# Skaarhoj_BI8-1x12CAP3slim.net
KiCad netlist of a schematic drawn in EAGLE
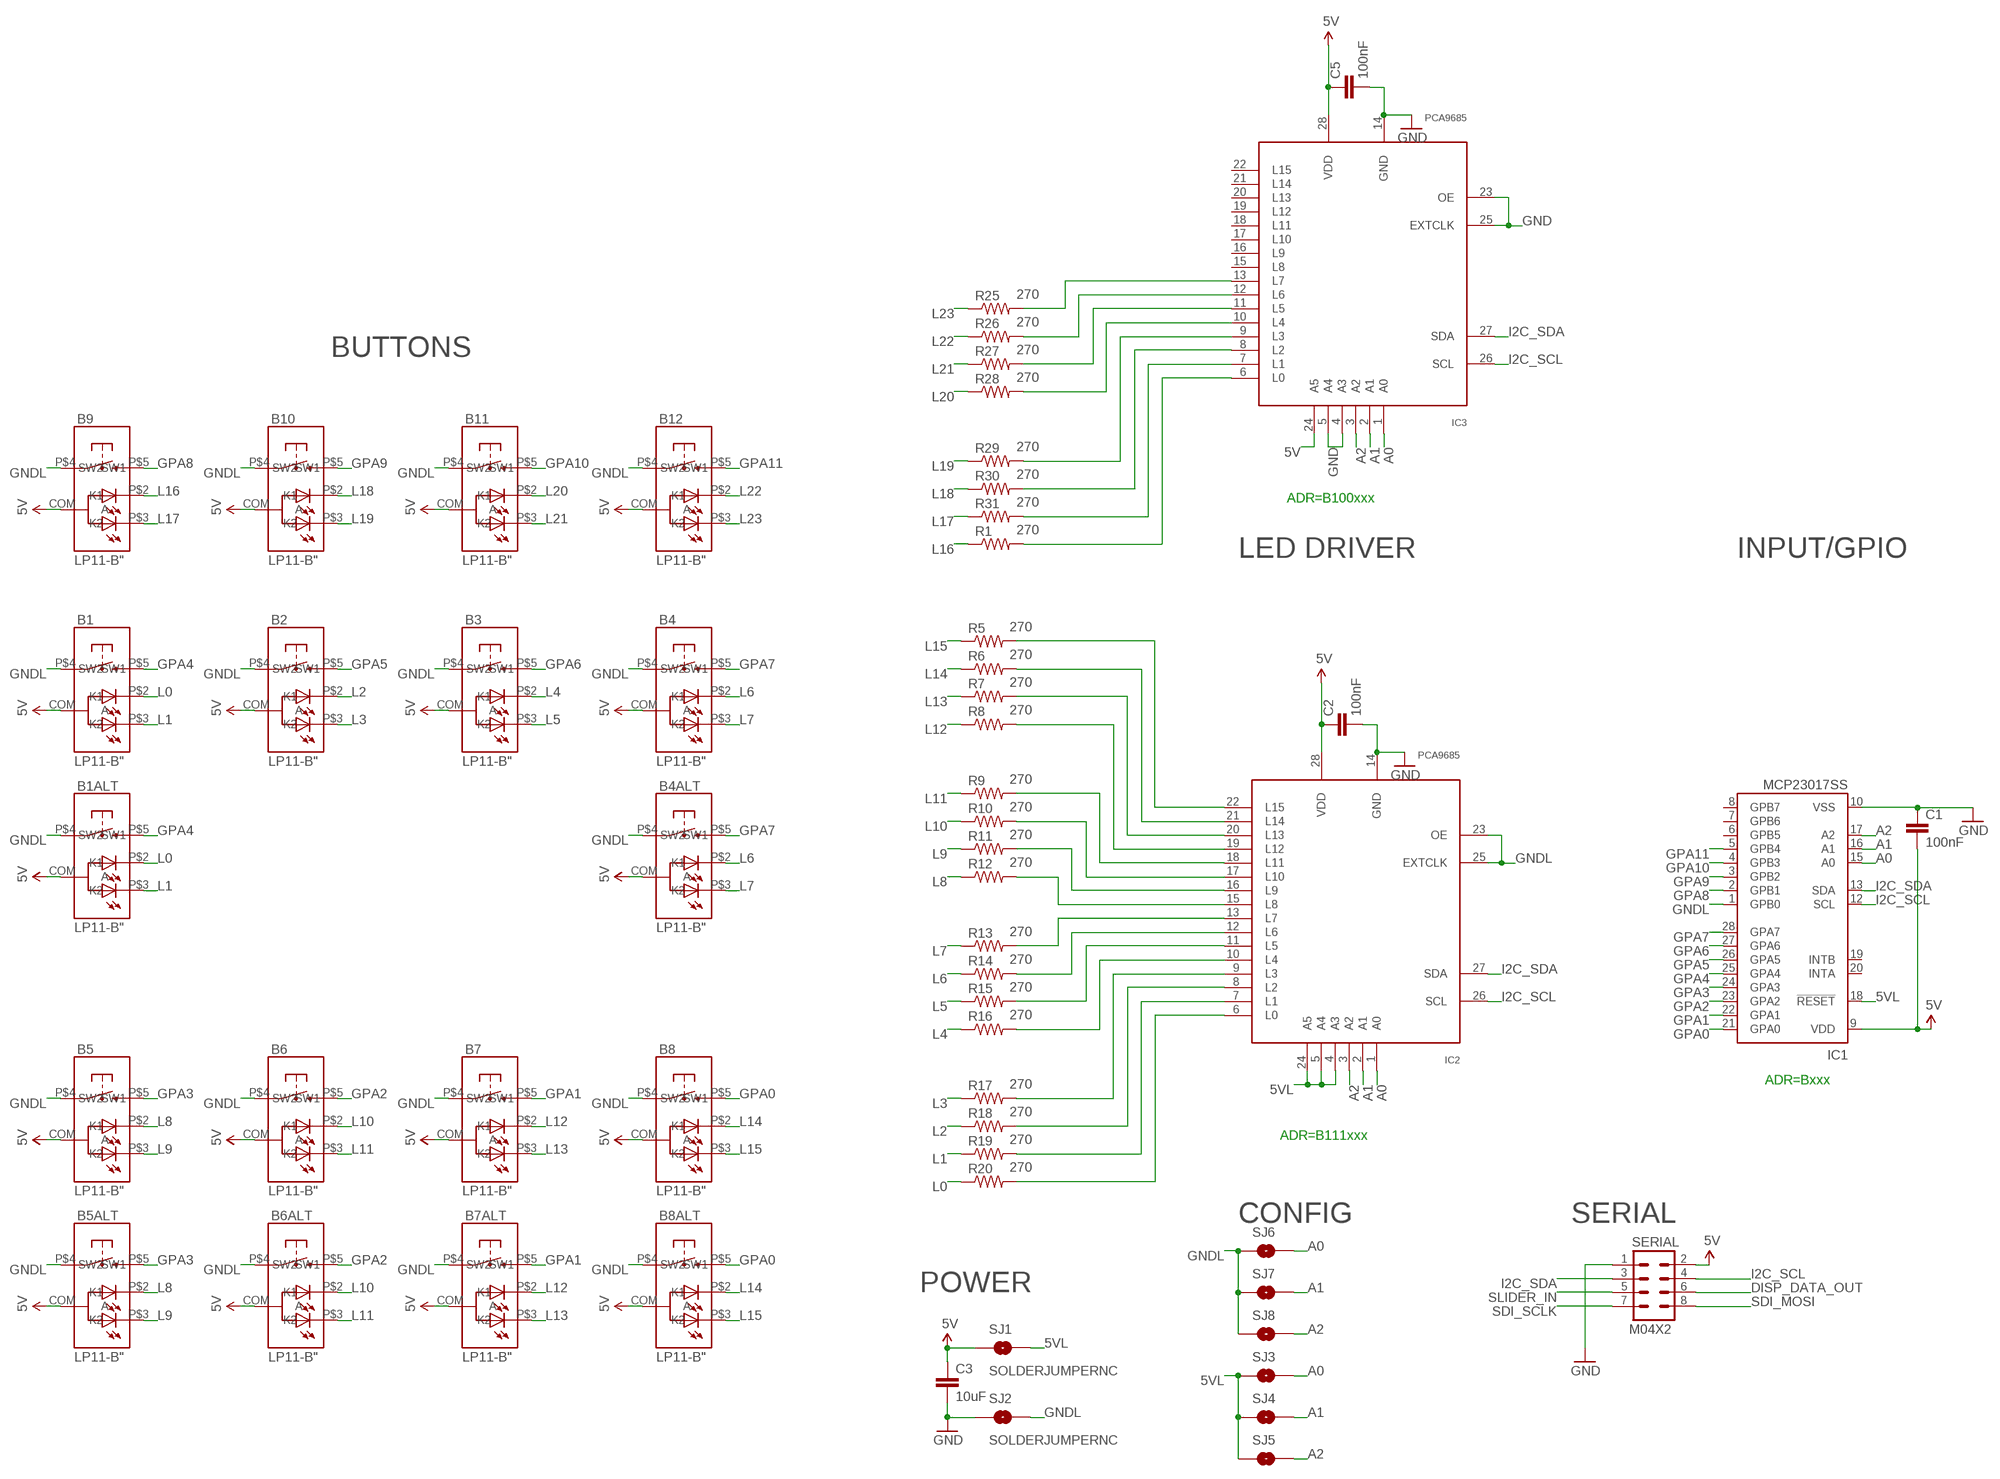
[diagram p0: schematic, sheet 1]

(export (version "E")
  (design (tool "Eeschema 10.0.6"))
  (components
    (comp (ref "B1")
      (value "LP11-B\"")
      (footprint "eagle-import:LP11")
      (libsource (lib "eagle-import") (part "LP11-B{dblquote}"))
    )
    (comp (ref "B1ALT")
      (value "LP11-B\"")
      (footprint "eagle-import:LP11")
      (libsource (lib "eagle-import") (part "LP11-B{dblquote}"))
    )
    (comp (ref "B2")
      (value "LP11-B\"")
      (footprint "eagle-import:LP11")
      (libsource (lib "eagle-import") (part "LP11-B{dblquote}"))
    )
    (comp (ref "B3")
      (value "LP11-B\"")
      (footprint "eagle-import:LP11")
      (libsource (lib "eagle-import") (part "LP11-B{dblquote}"))
    )
    (comp (ref "B4")
      (value "LP11-B\"")
      (footprint "eagle-import:LP11")
      (libsource (lib "eagle-import") (part "LP11-B{dblquote}"))
    )
    (comp (ref "B4ALT")
      (value "LP11-B\"")
      (footprint "eagle-import:LP11")
      (libsource (lib "eagle-import") (part "LP11-B{dblquote}"))
    )
    (comp (ref "B5")
      (value "LP11-B\"")
      (footprint "eagle-import:LP11")
      (libsource (lib "eagle-import") (part "LP11-B{dblquote}"))
    )
    (comp (ref "B5ALT")
      (value "LP11-B\"")
      (footprint "eagle-import:LP11")
      (libsource (lib "eagle-import") (part "LP11-B{dblquote}"))
    )
    (comp (ref "B6")
      (value "LP11-B\"")
      (footprint "eagle-import:LP11")
      (libsource (lib "eagle-import") (part "LP11-B{dblquote}"))
    )
    (comp (ref "B6ALT")
      (value "LP11-B\"")
      (footprint "eagle-import:LP11")
      (libsource (lib "eagle-import") (part "LP11-B{dblquote}"))
    )
    (comp (ref "B7")
      (value "LP11-B\"")
      (footprint "eagle-import:LP11")
      (libsource (lib "eagle-import") (part "LP11-B{dblquote}"))
    )
    (comp (ref "B7ALT")
      (value "LP11-B\"")
      (footprint "eagle-import:LP11")
      (libsource (lib "eagle-import") (part "LP11-B{dblquote}"))
    )
    (comp (ref "B8")
      (value "LP11-B\"")
      (footprint "eagle-import:LP11")
      (libsource (lib "eagle-import") (part "LP11-B{dblquote}"))
    )
    (comp (ref "B8ALT")
      (value "LP11-B\"")
      (footprint "eagle-import:LP11")
      (libsource (lib "eagle-import") (part "LP11-B{dblquote}"))
    )
    (comp (ref "B9")
      (value "LP11-B\"")
      (footprint "eagle-import:LP11")
      (libsource (lib "eagle-import") (part "LP11-B{dblquote}"))
    )
    (comp (ref "B10")
      (value "LP11-B\"")
      (footprint "eagle-import:LP11")
      (libsource (lib "eagle-import") (part "LP11-B{dblquote}"))
    )
    (comp (ref "B11")
      (value "LP11-B\"")
      (footprint "eagle-import:LP11")
      (libsource (lib "eagle-import") (part "LP11-B{dblquote}"))
    )
    (comp (ref "B12")
      (value "LP11-B\"")
      (footprint "eagle-import:LP11")
      (libsource (lib "eagle-import") (part "LP11-B{dblquote}"))
    )
    (comp (ref "C1")
      (value "100nF")
      (footprint "eagle-import:0603-CAP")
      (libsource (lib "eagle-import") (part "CAP0603-CAP"))
    )
    (comp (ref "C2")
      (value "100nF")
      (footprint "eagle-import:0603-CAP")
      (libsource (lib "eagle-import") (part "CAP0603-CAP"))
    )
    (comp (ref "C3")
      (value "10uF")
      (footprint "eagle-import:0805")
      (libsource (lib "eagle-import") (part "CAP0805"))
    )
    (comp (ref "C5")
      (value "100nF")
      (footprint "eagle-import:0603-CAP")
      (libsource (lib "eagle-import") (part "CAP0603-CAP"))
    )
    (comp (ref "IC1")
      (value "MCP23017SS")
      (footprint "eagle-import:SSOP28")
      (fields
        (field (name "MF") "MICROCHIP")
        (field (name "MPN") "MCP23017-E/SS")
        (field (name "MPN_1") "MCP23017-E/SS")
        (field (name "OC_FARNELL") "1467674")
        (field (name "OC_NEWARK") "31K2960")
      )
      (libsource (lib "eagle-import") (part "MCP23017SS"))
    )
    (comp (ref "IC2")
      (value "PCA9685")
      (footprint "eagle-import:TSSOP28")
      (libsource (lib "eagle-import") (part "PCA9685"))
    )
    (comp (ref "IC3")
      (value "PCA9685")
      (footprint "eagle-import:TSSOP28")
      (libsource (lib "eagle-import") (part "PCA9685"))
    )
    (comp (ref "R1")
      (value "270")
      (footprint "eagle-import:0603-RES")
      (libsource (lib "eagle-import") (part "RESISTOR0603-RES"))
    )
    (comp (ref "R5")
      (value "270")
      (footprint "eagle-import:0603-RES")
      (libsource (lib "eagle-import") (part "RESISTOR0603-RES"))
    )
    (comp (ref "R6")
      (value "270")
      (footprint "eagle-import:0603-RES")
      (libsource (lib "eagle-import") (part "RESISTOR0603-RES"))
    )
    (comp (ref "R7")
      (value "270")
      (footprint "eagle-import:0603-RES")
      (libsource (lib "eagle-import") (part "RESISTOR0603-RES"))
    )
    (comp (ref "R8")
      (value "270")
      (footprint "eagle-import:0603-RES")
      (libsource (lib "eagle-import") (part "RESISTOR0603-RES"))
    )
    (comp (ref "R9")
      (value "270")
      (footprint "eagle-import:0603-RES")
      (libsource (lib "eagle-import") (part "RESISTOR0603-RES"))
    )
    (comp (ref "R10")
      (value "270")
      (footprint "eagle-import:0603-RES")
      (libsource (lib "eagle-import") (part "RESISTOR0603-RES"))
    )
    (comp (ref "R11")
      (value "270")
      (footprint "eagle-import:0603-RES")
      (libsource (lib "eagle-import") (part "RESISTOR0603-RES"))
    )
    (comp (ref "R12")
      (value "270")
      (footprint "eagle-import:0603-RES")
      (libsource (lib "eagle-import") (part "RESISTOR0603-RES"))
    )
    (comp (ref "R13")
      (value "270")
      (footprint "eagle-import:0603-RES")
      (libsource (lib "eagle-import") (part "RESISTOR0603-RES"))
    )
    (comp (ref "R14")
      (value "270")
      (footprint "eagle-import:0603-RES")
      (libsource (lib "eagle-import") (part "RESISTOR0603-RES"))
    )
    (comp (ref "R15")
      (value "270")
      (footprint "eagle-import:0603-RES")
      (libsource (lib "eagle-import") (part "RESISTOR0603-RES"))
    )
    (comp (ref "R16")
      (value "270")
      (footprint "eagle-import:0603-RES")
      (libsource (lib "eagle-import") (part "RESISTOR0603-RES"))
    )
    (comp (ref "R17")
      (value "270")
      (footprint "eagle-import:0603-RES")
      (libsource (lib "eagle-import") (part "RESISTOR0603-RES"))
    )
    (comp (ref "R18")
      (value "270")
      (footprint "eagle-import:0603-RES")
      (libsource (lib "eagle-import") (part "RESISTOR0603-RES"))
    )
    (comp (ref "R19")
      (value "270")
      (footprint "eagle-import:0603-RES")
      (libsource (lib "eagle-import") (part "RESISTOR0603-RES"))
    )
    (comp (ref "R20")
      (value "270")
      (footprint "eagle-import:0603-RES")
      (libsource (lib "eagle-import") (part "RESISTOR0603-RES"))
    )
    (comp (ref "R25")
      (value "270")
      (footprint "eagle-import:0603-RES")
      (libsource (lib "eagle-import") (part "RESISTOR0603-RES"))
    )
    (comp (ref "R26")
      (value "270")
      (footprint "eagle-import:0603-RES")
      (libsource (lib "eagle-import") (part "RESISTOR0603-RES"))
    )
    (comp (ref "R27")
      (value "270")
      (footprint "eagle-import:0603-RES")
      (libsource (lib "eagle-import") (part "RESISTOR0603-RES"))
    )
    (comp (ref "R28")
      (value "270")
      (footprint "eagle-import:0603-RES")
      (libsource (lib "eagle-import") (part "RESISTOR0603-RES"))
    )
    (comp (ref "R29")
      (value "270")
      (footprint "eagle-import:0603-RES")
      (libsource (lib "eagle-import") (part "RESISTOR0603-RES"))
    )
    (comp (ref "R30")
      (value "270")
      (footprint "eagle-import:0603-RES")
      (libsource (lib "eagle-import") (part "RESISTOR0603-RES"))
    )
    (comp (ref "R31")
      (value "270")
      (footprint "eagle-import:0603-RES")
      (libsource (lib "eagle-import") (part "RESISTOR0603-RES"))
    )
    (comp (ref "SERIAL")
      (value "M04X2")
      (footprint "eagle-import:2X4")
      (libsource (lib "eagle-import") (part "M04X2"))
    )
    (comp (ref "SJ1")
      (value "SOLDERJUMPERNC")
      (footprint "eagle-import:SJ_2S")
      (libsource (lib "eagle-import") (part "SOLDERJUMPERNC"))
    )
    (comp (ref "SJ2")
      (value "SOLDERJUMPERNC")
      (footprint "eagle-import:SJ_2S")
      (libsource (lib "eagle-import") (part "SOLDERJUMPERNC"))
    )
    (comp (ref "SJ3")
      (value "SOLDERJUMPERNC")
      (footprint "eagle-import:SJ_2S")
      (libsource (lib "eagle-import") (part "SOLDERJUMPERNC"))
    )
    (comp (ref "SJ4")
      (value "SOLDERJUMPERNC")
      (footprint "eagle-import:SJ_2S")
      (libsource (lib "eagle-import") (part "SOLDERJUMPERNC"))
    )
    (comp (ref "SJ5")
      (value "SOLDERJUMPERNC")
      (footprint "eagle-import:SJ_2S")
      (libsource (lib "eagle-import") (part "SOLDERJUMPERNC"))
    )
    (comp (ref "SJ6")
      (value "SOLDERJUMPERNC")
      (footprint "eagle-import:SJ_2S")
      (libsource (lib "eagle-import") (part "SOLDERJUMPERNC"))
    )
    (comp (ref "SJ7")
      (value "SOLDERJUMPERNC")
      (footprint "eagle-import:SJ_2S")
      (libsource (lib "eagle-import") (part "SOLDERJUMPERNC"))
    )
    (comp (ref "SJ8")
      (value "SOLDERJUMPERNC")
      (footprint "eagle-import:SJ_2S")
      (libsource (lib "eagle-import") (part "SOLDERJUMPERNC"))
    )
  )
  (nets
    (net (code "1") (name "/5VL") (class "Default")
      (node (ref "IC1") (pin "18") (pinfunction "~{RESET}_18") (pintype "input"))
      (node (ref "IC2") (pin "24") (pinfunction "A5_24") (pintype "input"))
      (node (ref "IC2") (pin "4") (pinfunction "A3_4") (pintype "input"))
      (node (ref "IC2") (pin "5") (pinfunction "A4_5") (pintype "input"))
      (node (ref "SJ1") (pin "2") (pinfunction "2_2") (pintype "passive"))
      (node (ref "SJ3") (pin "1") (pinfunction "1_1") (pintype "passive"))
      (node (ref "SJ4") (pin "1") (pinfunction "1_1") (pintype "passive"))
      (node (ref "SJ5") (pin "1") (pinfunction "1_1") (pintype "passive"))
    )
    (net (code "2") (name "/A0") (class "Default")
      (node (ref "IC1") (pin "15") (pinfunction "A0_15") (pintype "input"))
      (node (ref "IC2") (pin "1") (pinfunction "A0_1") (pintype "input"))
      (node (ref "IC3") (pin "1") (pinfunction "A0_1") (pintype "input"))
      (node (ref "SJ3") (pin "2") (pinfunction "2_2") (pintype "passive"))
      (node (ref "SJ6") (pin "2") (pinfunction "2_2") (pintype "passive"))
    )
    (net (code "3") (name "/A1") (class "Default")
      (node (ref "IC1") (pin "16") (pinfunction "A1_16") (pintype "input"))
      (node (ref "IC2") (pin "2") (pinfunction "A1_2") (pintype "input"))
      (node (ref "IC3") (pin "2") (pinfunction "A1_2") (pintype "input"))
      (node (ref "SJ4") (pin "2") (pinfunction "2_2") (pintype "passive"))
      (node (ref "SJ7") (pin "2") (pinfunction "2_2") (pintype "passive"))
    )
    (net (code "4") (name "/A2") (class "Default")
      (node (ref "IC1") (pin "17") (pinfunction "A2_17") (pintype "input"))
      (node (ref "IC2") (pin "3") (pinfunction "A2_3") (pintype "input"))
      (node (ref "IC3") (pin "3") (pinfunction "A2_3") (pintype "input"))
      (node (ref "SJ5") (pin "2") (pinfunction "2_2") (pintype "passive"))
      (node (ref "SJ8") (pin "2") (pinfunction "2_2") (pintype "passive"))
    )
    (net (code "5") (name "/DISP_DATA_OUT") (class "Default")
      (node (ref "SERIAL") (pin "6") (pinfunction "6_6") (pintype "passive"))
    )
    (net (code "6") (name "/GNDL") (class "Default")
      (node (ref "B1") (pin "P$4") (pinfunction "SW1_P$4") (pintype "bidirectional"))
      (node (ref "B10") (pin "P$4") (pinfunction "SW1_P$4") (pintype "bidirectional"))
      (node (ref "B11") (pin "P$4") (pinfunction "SW1_P$4") (pintype "bidirectional"))
      (node (ref "B12") (pin "P$4") (pinfunction "SW1_P$4") (pintype "bidirectional"))
      (node (ref "B1ALT") (pin "P$4") (pinfunction "SW1_P$4") (pintype "bidirectional"))
      (node (ref "B2") (pin "P$4") (pinfunction "SW1_P$4") (pintype "bidirectional"))
      (node (ref "B3") (pin "P$4") (pinfunction "SW1_P$4") (pintype "bidirectional"))
      (node (ref "B4") (pin "P$4") (pinfunction "SW1_P$4") (pintype "bidirectional"))
      (node (ref "B4ALT") (pin "P$4") (pinfunction "SW1_P$4") (pintype "bidirectional"))
      (node (ref "B5") (pin "P$4") (pinfunction "SW1_P$4") (pintype "bidirectional"))
      (node (ref "B5ALT") (pin "P$4") (pinfunction "SW1_P$4") (pintype "bidirectional"))
      (node (ref "B6") (pin "P$4") (pinfunction "SW1_P$4") (pintype "bidirectional"))
      (node (ref "B6ALT") (pin "P$4") (pinfunction "SW1_P$4") (pintype "bidirectional"))
      (node (ref "B7") (pin "P$4") (pinfunction "SW1_P$4") (pintype "bidirectional"))
      (node (ref "B7ALT") (pin "P$4") (pinfunction "SW1_P$4") (pintype "bidirectional"))
      (node (ref "B8") (pin "P$4") (pinfunction "SW1_P$4") (pintype "bidirectional"))
      (node (ref "B8ALT") (pin "P$4") (pinfunction "SW1_P$4") (pintype "bidirectional"))
      (node (ref "B9") (pin "P$4") (pinfunction "SW1_P$4") (pintype "bidirectional"))
      (node (ref "IC1") (pin "1") (pinfunction "GPB0_1") (pintype "bidirectional"))
      (node (ref "IC2") (pin "23") (pinfunction "OE_23") (pintype "input"))
      (node (ref "IC2") (pin "25") (pinfunction "EXTCLK_25") (pintype "input"))
      (node (ref "SJ2") (pin "2") (pinfunction "2_2") (pintype "passive"))
      (node (ref "SJ6") (pin "1") (pinfunction "1_1") (pintype "passive"))
      (node (ref "SJ7") (pin "1") (pinfunction "1_1") (pintype "passive"))
      (node (ref "SJ8") (pin "1") (pinfunction "1_1") (pintype "passive"))
    )
    (net (code "7") (name "/GPA0") (class "Default")
      (node (ref "B8") (pin "P$5") (pinfunction "SW2_P$5") (pintype "bidirectional"))
      (node (ref "B8ALT") (pin "P$5") (pinfunction "SW2_P$5") (pintype "bidirectional"))
      (node (ref "IC1") (pin "21") (pinfunction "GPA0_21") (pintype "bidirectional"))
    )
    (net (code "8") (name "/GPA1") (class "Default")
      (node (ref "B7") (pin "P$5") (pinfunction "SW2_P$5") (pintype "bidirectional"))
      (node (ref "B7ALT") (pin "P$5") (pinfunction "SW2_P$5") (pintype "bidirectional"))
      (node (ref "IC1") (pin "22") (pinfunction "GPA1_22") (pintype "bidirectional"))
    )
    (net (code "9") (name "/GPA2") (class "Default")
      (node (ref "B6") (pin "P$5") (pinfunction "SW2_P$5") (pintype "bidirectional"))
      (node (ref "B6ALT") (pin "P$5") (pinfunction "SW2_P$5") (pintype "bidirectional"))
      (node (ref "IC1") (pin "23") (pinfunction "GPA2_23") (pintype "bidirectional"))
    )
    (net (code "10") (name "/GPA3") (class "Default")
      (node (ref "B5") (pin "P$5") (pinfunction "SW2_P$5") (pintype "bidirectional"))
      (node (ref "B5ALT") (pin "P$5") (pinfunction "SW2_P$5") (pintype "bidirectional"))
      (node (ref "IC1") (pin "24") (pinfunction "GPA3_24") (pintype "bidirectional"))
    )
    (net (code "11") (name "/GPA4") (class "Default")
      (node (ref "B1") (pin "P$5") (pinfunction "SW2_P$5") (pintype "bidirectional"))
      (node (ref "B1ALT") (pin "P$5") (pinfunction "SW2_P$5") (pintype "bidirectional"))
      (node (ref "IC1") (pin "25") (pinfunction "GPA4_25") (pintype "bidirectional"))
    )
    (net (code "12") (name "/GPA5") (class "Default")
      (node (ref "B2") (pin "P$5") (pinfunction "SW2_P$5") (pintype "bidirectional"))
      (node (ref "IC1") (pin "26") (pinfunction "GPA5_26") (pintype "bidirectional"))
    )
    (net (code "13") (name "/GPA6") (class "Default")
      (node (ref "B3") (pin "P$5") (pinfunction "SW2_P$5") (pintype "bidirectional"))
      (node (ref "IC1") (pin "27") (pinfunction "GPA6_27") (pintype "bidirectional"))
    )
    (net (code "14") (name "/GPA7") (class "Default")
      (node (ref "B4") (pin "P$5") (pinfunction "SW2_P$5") (pintype "bidirectional"))
      (node (ref "B4ALT") (pin "P$5") (pinfunction "SW2_P$5") (pintype "bidirectional"))
      (node (ref "IC1") (pin "28") (pinfunction "GPA7_28") (pintype "bidirectional"))
    )
    (net (code "15") (name "/GPA8") (class "Default")
      (node (ref "B9") (pin "P$5") (pinfunction "SW2_P$5") (pintype "bidirectional"))
      (node (ref "IC1") (pin "2") (pinfunction "GPB1_2") (pintype "bidirectional"))
    )
    (net (code "16") (name "/GPA9") (class "Default")
      (node (ref "B10") (pin "P$5") (pinfunction "SW2_P$5") (pintype "bidirectional"))
      (node (ref "IC1") (pin "3") (pinfunction "GPB2_3") (pintype "bidirectional"))
    )
    (net (code "17") (name "/GPA10") (class "Default")
      (node (ref "B11") (pin "P$5") (pinfunction "SW2_P$5") (pintype "bidirectional"))
      (node (ref "IC1") (pin "4") (pinfunction "GPB3_4") (pintype "bidirectional"))
    )
    (net (code "18") (name "/GPA11") (class "Default")
      (node (ref "B12") (pin "P$5") (pinfunction "SW2_P$5") (pintype "bidirectional"))
      (node (ref "IC1") (pin "5") (pinfunction "GPB4_5") (pintype "bidirectional"))
    )
    (net (code "19") (name "/I2C_SCL") (class "Default")
      (node (ref "IC1") (pin "12") (pinfunction "SCL_12") (pintype "input"))
      (node (ref "IC2") (pin "26") (pinfunction "SCL_26") (pintype "input"))
      (node (ref "IC3") (pin "26") (pinfunction "SCL_26") (pintype "input"))
      (node (ref "SERIAL") (pin "4") (pinfunction "4_4") (pintype "passive"))
    )
    (net (code "20") (name "/I2C_SDA") (class "Default")
      (node (ref "IC1") (pin "13") (pinfunction "SDA_13") (pintype "bidirectional"))
      (node (ref "IC2") (pin "27") (pinfunction "SDA_27") (pintype "input"))
      (node (ref "IC3") (pin "27") (pinfunction "SDA_27") (pintype "input"))
      (node (ref "SERIAL") (pin "3") (pinfunction "3_3") (pintype "passive"))
    )
    (net (code "21") (name "/L0") (class "Default")
      (node (ref "B1") (pin "P$2") (pinfunction "K1_P$2") (pintype "bidirectional"))
      (node (ref "B1ALT") (pin "P$2") (pinfunction "K1_P$2") (pintype "bidirectional"))
      (node (ref "R20") (pin "1") (pinfunction "1_1") (pintype "passive"))
    )
    (net (code "22") (name "/L1") (class "Default")
      (node (ref "B1") (pin "P$3") (pinfunction "K2_P$3") (pintype "bidirectional"))
      (node (ref "B1ALT") (pin "P$3") (pinfunction "K2_P$3") (pintype "bidirectional"))
      (node (ref "R19") (pin "1") (pinfunction "1_1") (pintype "passive"))
    )
    (net (code "23") (name "/L2") (class "Default")
      (node (ref "B2") (pin "P$2") (pinfunction "K1_P$2") (pintype "bidirectional"))
      (node (ref "R18") (pin "1") (pinfunction "1_1") (pintype "passive"))
    )
    (net (code "24") (name "/L3") (class "Default")
      (node (ref "B2") (pin "P$3") (pinfunction "K2_P$3") (pintype "bidirectional"))
      (node (ref "R17") (pin "1") (pinfunction "1_1") (pintype "passive"))
    )
    (net (code "25") (name "/L4") (class "Default")
      (node (ref "B3") (pin "P$2") (pinfunction "K1_P$2") (pintype "bidirectional"))
      (node (ref "R16") (pin "1") (pinfunction "1_1") (pintype "passive"))
    )
    (net (code "26") (name "/L5") (class "Default")
      (node (ref "B3") (pin "P$3") (pinfunction "K2_P$3") (pintype "bidirectional"))
      (node (ref "R15") (pin "1") (pinfunction "1_1") (pintype "passive"))
    )
    (net (code "27") (name "/L6") (class "Default")
      (node (ref "B4") (pin "P$2") (pinfunction "K1_P$2") (pintype "bidirectional"))
      (node (ref "B4ALT") (pin "P$2") (pinfunction "K1_P$2") (pintype "bidirectional"))
      (node (ref "R14") (pin "1") (pinfunction "1_1") (pintype "passive"))
    )
    (net (code "28") (name "/L7") (class "Default")
      (node (ref "B4") (pin "P$3") (pinfunction "K2_P$3") (pintype "bidirectional"))
      (node (ref "B4ALT") (pin "P$3") (pinfunction "K2_P$3") (pintype "bidirectional"))
      (node (ref "R13") (pin "1") (pinfunction "1_1") (pintype "passive"))
    )
    (net (code "29") (name "/L8") (class "Default")
      (node (ref "B5") (pin "P$2") (pinfunction "K1_P$2") (pintype "bidirectional"))
      (node (ref "B5ALT") (pin "P$2") (pinfunction "K1_P$2") (pintype "bidirectional"))
      (node (ref "R12") (pin "1") (pinfunction "1_1") (pintype "passive"))
    )
    (net (code "30") (name "/L9") (class "Default")
      (node (ref "B5") (pin "P$3") (pinfunction "K2_P$3") (pintype "bidirectional"))
      (node (ref "B5ALT") (pin "P$3") (pinfunction "K2_P$3") (pintype "bidirectional"))
      (node (ref "R11") (pin "1") (pinfunction "1_1") (pintype "passive"))
    )
    (net (code "31") (name "/L10") (class "Default")
      (node (ref "B6") (pin "P$2") (pinfunction "K1_P$2") (pintype "bidirectional"))
      (node (ref "B6ALT") (pin "P$2") (pinfunction "K1_P$2") (pintype "bidirectional"))
      (node (ref "R10") (pin "1") (pinfunction "1_1") (pintype "passive"))
    )
    (net (code "32") (name "/L11") (class "Default")
      (node (ref "B6") (pin "P$3") (pinfunction "K2_P$3") (pintype "bidirectional"))
      (node (ref "B6ALT") (pin "P$3") (pinfunction "K2_P$3") (pintype "bidirectional"))
      (node (ref "R9") (pin "1") (pinfunction "1_1") (pintype "passive"))
    )
    (net (code "33") (name "/L12") (class "Default")
      (node (ref "B7") (pin "P$2") (pinfunction "K1_P$2") (pintype "bidirectional"))
      (node (ref "B7ALT") (pin "P$2") (pinfunction "K1_P$2") (pintype "bidirectional"))
      (node (ref "R8") (pin "1") (pinfunction "1_1") (pintype "passive"))
    )
    (net (code "34") (name "/L13") (class "Default")
      (node (ref "B7") (pin "P$3") (pinfunction "K2_P$3") (pintype "bidirectional"))
      (node (ref "B7ALT") (pin "P$3") (pinfunction "K2_P$3") (pintype "bidirectional"))
      (node (ref "R7") (pin "1") (pinfunction "1_1") (pintype "passive"))
    )
    (net (code "35") (name "/L14") (class "Default")
      (node (ref "B8") (pin "P$2") (pinfunction "K1_P$2") (pintype "bidirectional"))
      (node (ref "B8ALT") (pin "P$2") (pinfunction "K1_P$2") (pintype "bidirectional"))
      (node (ref "R6") (pin "1") (pinfunction "1_1") (pintype "passive"))
    )
    (net (code "36") (name "/L15") (class "Default")
      (node (ref "B8") (pin "P$3") (pinfunction "K2_P$3") (pintype "bidirectional"))
      (node (ref "B8ALT") (pin "P$3") (pinfunction "K2_P$3") (pintype "bidirectional"))
      (node (ref "R5") (pin "1") (pinfunction "1_1") (pintype "passive"))
    )
    (net (code "37") (name "/L16") (class "Default")
      (node (ref "B9") (pin "P$2") (pinfunction "K1_P$2") (pintype "bidirectional"))
      (node (ref "R1") (pin "1") (pinfunction "1_1") (pintype "passive"))
    )
    (net (code "38") (name "/L17") (class "Default")
      (node (ref "B9") (pin "P$3") (pinfunction "K2_P$3") (pintype "bidirectional"))
      (node (ref "R31") (pin "1") (pinfunction "1_1") (pintype "passive"))
    )
    (net (code "39") (name "/L18") (class "Default")
      (node (ref "B10") (pin "P$2") (pinfunction "K1_P$2") (pintype "bidirectional"))
      (node (ref "R30") (pin "1") (pinfunction "1_1") (pintype "passive"))
    )
    (net (code "40") (name "/L19") (class "Default")
      (node (ref "B10") (pin "P$3") (pinfunction "K2_P$3") (pintype "bidirectional"))
      (node (ref "R29") (pin "1") (pinfunction "1_1") (pintype "passive"))
    )
    (net (code "41") (name "/L20") (class "Default")
      (node (ref "B11") (pin "P$2") (pinfunction "K1_P$2") (pintype "bidirectional"))
      (node (ref "R28") (pin "1") (pinfunction "1_1") (pintype "passive"))
    )
    (net (code "42") (name "/L21") (class "Default")
      (node (ref "B11") (pin "P$3") (pinfunction "K2_P$3") (pintype "bidirectional"))
      (node (ref "R27") (pin "1") (pinfunction "1_1") (pintype "passive"))
    )
    (net (code "43") (name "/L22") (class "Default")
      (node (ref "B12") (pin "P$2") (pinfunction "K1_P$2") (pintype "bidirectional"))
      (node (ref "R26") (pin "1") (pinfunction "1_1") (pintype "passive"))
    )
    (net (code "44") (name "/L23") (class "Default")
      (node (ref "B12") (pin "P$3") (pinfunction "K2_P$3") (pintype "bidirectional"))
      (node (ref "R25") (pin "1") (pinfunction "1_1") (pintype "passive"))
    )
    (net (code "45") (name "/SDI_MOSI") (class "Default")
      (node (ref "SERIAL") (pin "8") (pinfunction "8_8") (pintype "passive"))
    )
    (net (code "46") (name "/SDI_SCLK") (class "Default")
      (node (ref "SERIAL") (pin "7") (pinfunction "7_7") (pintype "passive"))
    )
    (net (code "47") (name "/SLIDER_IN") (class "Default")
      (node (ref "SERIAL") (pin "5") (pinfunction "5_5") (pintype "passive"))
    )
    (net (code "48") (name "5V") (class "Default")
      (node (ref "B1") (pin "COM") (pinfunction "A_COM") (pintype "bidirectional"))
      (node (ref "B10") (pin "COM") (pinfunction "A_COM") (pintype "bidirectional"))
      (node (ref "B11") (pin "COM") (pinfunction "A_COM") (pintype "bidirectional"))
      (node (ref "B12") (pin "COM") (pinfunction "A_COM") (pintype "bidirectional"))
      (node (ref "B1ALT") (pin "COM") (pinfunction "A_COM") (pintype "bidirectional"))
      (node (ref "B2") (pin "COM") (pinfunction "A_COM") (pintype "bidirectional"))
      (node (ref "B3") (pin "COM") (pinfunction "A_COM") (pintype "bidirectional"))
      (node (ref "B4") (pin "COM") (pinfunction "A_COM") (pintype "bidirectional"))
      (node (ref "B4ALT") (pin "COM") (pinfunction "A_COM") (pintype "bidirectional"))
      (node (ref "B5") (pin "COM") (pinfunction "A_COM") (pintype "bidirectional"))
      (node (ref "B5ALT") (pin "COM") (pinfunction "A_COM") (pintype "bidirectional"))
      (node (ref "B6") (pin "COM") (pinfunction "A_COM") (pintype "bidirectional"))
      (node (ref "B6ALT") (pin "COM") (pinfunction "A_COM") (pintype "bidirectional"))
      (node (ref "B7") (pin "COM") (pinfunction "A_COM") (pintype "bidirectional"))
      (node (ref "B7ALT") (pin "COM") (pinfunction "A_COM") (pintype "bidirectional"))
      (node (ref "B8") (pin "COM") (pinfunction "A_COM") (pintype "bidirectional"))
      (node (ref "B8ALT") (pin "COM") (pinfunction "A_COM") (pintype "bidirectional"))
      (node (ref "B9") (pin "COM") (pinfunction "A_COM") (pintype "bidirectional"))
      (node (ref "C1") (pin "2") (pinfunction "2_2") (pintype "passive"))
      (node (ref "C2") (pin "1") (pinfunction "1_1") (pintype "passive"))
      (node (ref "C3") (pin "1") (pinfunction "1_1") (pintype "passive"))
      (node (ref "C5") (pin "1") (pinfunction "1_1") (pintype "passive"))
      (node (ref "IC1") (pin "9") (pinfunction "VDD_9") (pintype "power_in"))
      (node (ref "IC2") (pin "28") (pinfunction "VDD_28") (pintype "power_in"))
      (node (ref "IC3") (pin "24") (pinfunction "A5_24") (pintype "input"))
      (node (ref "IC3") (pin "28") (pinfunction "VDD_28") (pintype "power_in"))
      (node (ref "SERIAL") (pin "2") (pinfunction "2_2") (pintype "passive"))
      (node (ref "SJ1") (pin "1") (pinfunction "1_1") (pintype "passive"))
    )
    (net (code "49") (name "GND") (class "Default")
      (node (ref "C1") (pin "1") (pinfunction "1_1") (pintype "passive"))
      (node (ref "C2") (pin "2") (pinfunction "2_2") (pintype "passive"))
      (node (ref "C3") (pin "2") (pinfunction "2_2") (pintype "passive"))
      (node (ref "C5") (pin "2") (pinfunction "2_2") (pintype "passive"))
      (node (ref "IC1") (pin "10") (pinfunction "VSS_10") (pintype "power_in"))
      (node (ref "IC2") (pin "14") (pinfunction "GND_14") (pintype "power_in"))
      (node (ref "IC3") (pin "14") (pinfunction "GND_14") (pintype "power_in"))
      (node (ref "IC3") (pin "23") (pinfunction "OE_23") (pintype "input"))
      (node (ref "IC3") (pin "25") (pinfunction "EXTCLK_25") (pintype "input"))
      (node (ref "IC3") (pin "4") (pinfunction "A3_4") (pintype "input"))
      (node (ref "IC3") (pin "5") (pinfunction "A4_5") (pintype "input"))
      (node (ref "SERIAL") (pin "1") (pinfunction "1_1") (pintype "passive"))
      (node (ref "SJ2") (pin "1") (pinfunction "1_1") (pintype "passive"))
    )
    (net (code "50") (name "Net-(IC2-L0)") (class "Default")
      (node (ref "IC2") (pin "6") (pinfunction "L0_6") (pintype "output"))
      (node (ref "R20") (pin "2") (pinfunction "2_2") (pintype "passive"))
    )
    (net (code "51") (name "Net-(IC2-L1)") (class "Default")
      (node (ref "IC2") (pin "7") (pinfunction "L1_7") (pintype "output"))
      (node (ref "R19") (pin "2") (pinfunction "2_2") (pintype "passive"))
    )
    (net (code "52") (name "Net-(IC2-L2)") (class "Default")
      (node (ref "IC2") (pin "8") (pinfunction "L2_8") (pintype "output"))
      (node (ref "R18") (pin "2") (pinfunction "2_2") (pintype "passive"))
    )
    (net (code "53") (name "Net-(IC2-L3)") (class "Default")
      (node (ref "IC2") (pin "9") (pinfunction "L3_9") (pintype "output"))
      (node (ref "R17") (pin "2") (pinfunction "2_2") (pintype "passive"))
    )
    (net (code "54") (name "Net-(IC2-L4)") (class "Default")
      (node (ref "IC2") (pin "10") (pinfunction "L4_10") (pintype "output"))
      (node (ref "R16") (pin "2") (pinfunction "2_2") (pintype "passive"))
    )
    (net (code "55") (name "Net-(IC2-L5)") (class "Default")
      (node (ref "IC2") (pin "11") (pinfunction "L5_11") (pintype "output"))
      (node (ref "R15") (pin "2") (pinfunction "2_2") (pintype "passive"))
    )
    (net (code "56") (name "Net-(IC2-L6)") (class "Default")
      (node (ref "IC2") (pin "12") (pinfunction "L6_12") (pintype "output"))
      (node (ref "R14") (pin "2") (pinfunction "2_2") (pintype "passive"))
    )
    (net (code "57") (name "Net-(IC2-L7)") (class "Default")
      (node (ref "IC2") (pin "13") (pinfunction "L7_13") (pintype "output"))
      (node (ref "R13") (pin "2") (pinfunction "2_2") (pintype "passive"))
    )
    (net (code "58") (name "Net-(IC2-L8)") (class "Default")
      (node (ref "IC2") (pin "15") (pinfunction "L8_15") (pintype "output"))
      (node (ref "R12") (pin "2") (pinfunction "2_2") (pintype "passive"))
    )
    (net (code "59") (name "Net-(IC2-L9)") (class "Default")
      (node (ref "IC2") (pin "16") (pinfunction "L9_16") (pintype "output"))
      (node (ref "R11") (pin "2") (pinfunction "2_2") (pintype "passive"))
    )
    (net (code "60") (name "Net-(IC2-L10)") (class "Default")
      (node (ref "IC2") (pin "17") (pinfunction "L10_17") (pintype "output"))
      (node (ref "R10") (pin "2") (pinfunction "2_2") (pintype "passive"))
    )
    (net (code "61") (name "Net-(IC2-L11)") (class "Default")
      (node (ref "IC2") (pin "18") (pinfunction "L11_18") (pintype "output"))
      (node (ref "R9") (pin "2") (pinfunction "2_2") (pintype "passive"))
    )
    (net (code "62") (name "Net-(IC2-L12)") (class "Default")
      (node (ref "IC2") (pin "19") (pinfunction "L12_19") (pintype "output"))
      (node (ref "R8") (pin "2") (pinfunction "2_2") (pintype "passive"))
    )
    (net (code "63") (name "Net-(IC2-L13)") (class "Default")
      (node (ref "IC2") (pin "20") (pinfunction "L13_20") (pintype "output"))
      (node (ref "R7") (pin "2") (pinfunction "2_2") (pintype "passive"))
    )
    (net (code "64") (name "Net-(IC2-L14)") (class "Default")
      (node (ref "IC2") (pin "21") (pinfunction "L14_21") (pintype "output"))
      (node (ref "R6") (pin "2") (pinfunction "2_2") (pintype "passive"))
    )
    (net (code "65") (name "Net-(IC2-L15)") (class "Default")
      (node (ref "IC2") (pin "22") (pinfunction "L15_22") (pintype "output"))
      (node (ref "R5") (pin "2") (pinfunction "2_2") (pintype "passive"))
    )
    (net (code "66") (name "Net-(IC3-L0)") (class "Default")
      (node (ref "IC3") (pin "6") (pinfunction "L0_6") (pintype "output"))
      (node (ref "R1") (pin "2") (pinfunction "2_2") (pintype "passive"))
    )
    (net (code "67") (name "Net-(IC3-L1)") (class "Default")
      (node (ref "IC3") (pin "7") (pinfunction "L1_7") (pintype "output"))
      (node (ref "R31") (pin "2") (pinfunction "2_2") (pintype "passive"))
    )
    (net (code "68") (name "Net-(IC3-L2)") (class "Default")
      (node (ref "IC3") (pin "8") (pinfunction "L2_8") (pintype "output"))
      (node (ref "R30") (pin "2") (pinfunction "2_2") (pintype "passive"))
    )
    (net (code "69") (name "Net-(IC3-L3)") (class "Default")
      (node (ref "IC3") (pin "9") (pinfunction "L3_9") (pintype "output"))
      (node (ref "R29") (pin "2") (pinfunction "2_2") (pintype "passive"))
    )
    (net (code "70") (name "Net-(IC3-L4)") (class "Default")
      (node (ref "IC3") (pin "10") (pinfunction "L4_10") (pintype "output"))
      (node (ref "R28") (pin "2") (pinfunction "2_2") (pintype "passive"))
    )
    (net (code "71") (name "Net-(IC3-L5)") (class "Default")
      (node (ref "IC3") (pin "11") (pinfunction "L5_11") (pintype "output"))
      (node (ref "R27") (pin "2") (pinfunction "2_2") (pintype "passive"))
    )
    (net (code "72") (name "Net-(IC3-L6)") (class "Default")
      (node (ref "IC3") (pin "12") (pinfunction "L6_12") (pintype "output"))
      (node (ref "R26") (pin "2") (pinfunction "2_2") (pintype "passive"))
    )
    (net (code "73") (name "Net-(IC3-L7)") (class "Default")
      (node (ref "IC3") (pin "13") (pinfunction "L7_13") (pintype "output"))
      (node (ref "R25") (pin "2") (pinfunction "2_2") (pintype "passive"))
    )
    (net (code "74") (name "unconnected-(IC1-GPB5-Pad6)") (class "Default")
      (node (ref "IC1") (pin "6") (pinfunction "GPB5_6") (pintype "bidirectional"))
    )
    (net (code "75") (name "unconnected-(IC1-GPB6-Pad7)") (class "Default")
      (node (ref "IC1") (pin "7") (pinfunction "GPB6_7") (pintype "bidirectional"))
    )
    (net (code "76") (name "unconnected-(IC1-GPB7-Pad8)") (class "Default")
      (node (ref "IC1") (pin "8") (pinfunction "GPB7_8") (pintype "bidirectional"))
    )
    (net (code "77") (name "unconnected-(IC1-INTA-Pad20)") (class "Default")
      (node (ref "IC1") (pin "20") (pinfunction "INTA_20") (pintype "output"))
    )
    (net (code "78") (name "unconnected-(IC1-INTB-Pad19)") (class "Default")
      (node (ref "IC1") (pin "19") (pinfunction "INTB_19") (pintype "output"))
    )
    (net (code "79") (name "unconnected-(IC3-L8-Pad15)") (class "Default")
      (node (ref "IC3") (pin "15") (pinfunction "L8_15") (pintype "output"))
    )
    (net (code "80") (name "unconnected-(IC3-L9-Pad16)") (class "Default")
      (node (ref "IC3") (pin "16") (pinfunction "L9_16") (pintype "output"))
    )
    (net (code "81") (name "unconnected-(IC3-L10-Pad17)") (class "Default")
      (node (ref "IC3") (pin "17") (pinfunction "L10_17") (pintype "output"))
    )
    (net (code "82") (name "unconnected-(IC3-L11-Pad18)") (class "Default")
      (node (ref "IC3") (pin "18") (pinfunction "L11_18") (pintype "output"))
    )
    (net (code "83") (name "unconnected-(IC3-L12-Pad19)") (class "Default")
      (node (ref "IC3") (pin "19") (pinfunction "L12_19") (pintype "output"))
    )
    (net (code "84") (name "unconnected-(IC3-L13-Pad20)") (class "Default")
      (node (ref "IC3") (pin "20") (pinfunction "L13_20") (pintype "output"))
    )
    (net (code "85") (name "unconnected-(IC3-L14-Pad21)") (class "Default")
      (node (ref "IC3") (pin "21") (pinfunction "L14_21") (pintype "output"))
    )
    (net (code "86") (name "unconnected-(IC3-L15-Pad22)") (class "Default")
      (node (ref "IC3") (pin "22") (pinfunction "L15_22") (pintype "output"))
    )
  )
)
